# 1wire_temp.net
KiCad netlist of a schematic drawn in EAGLE
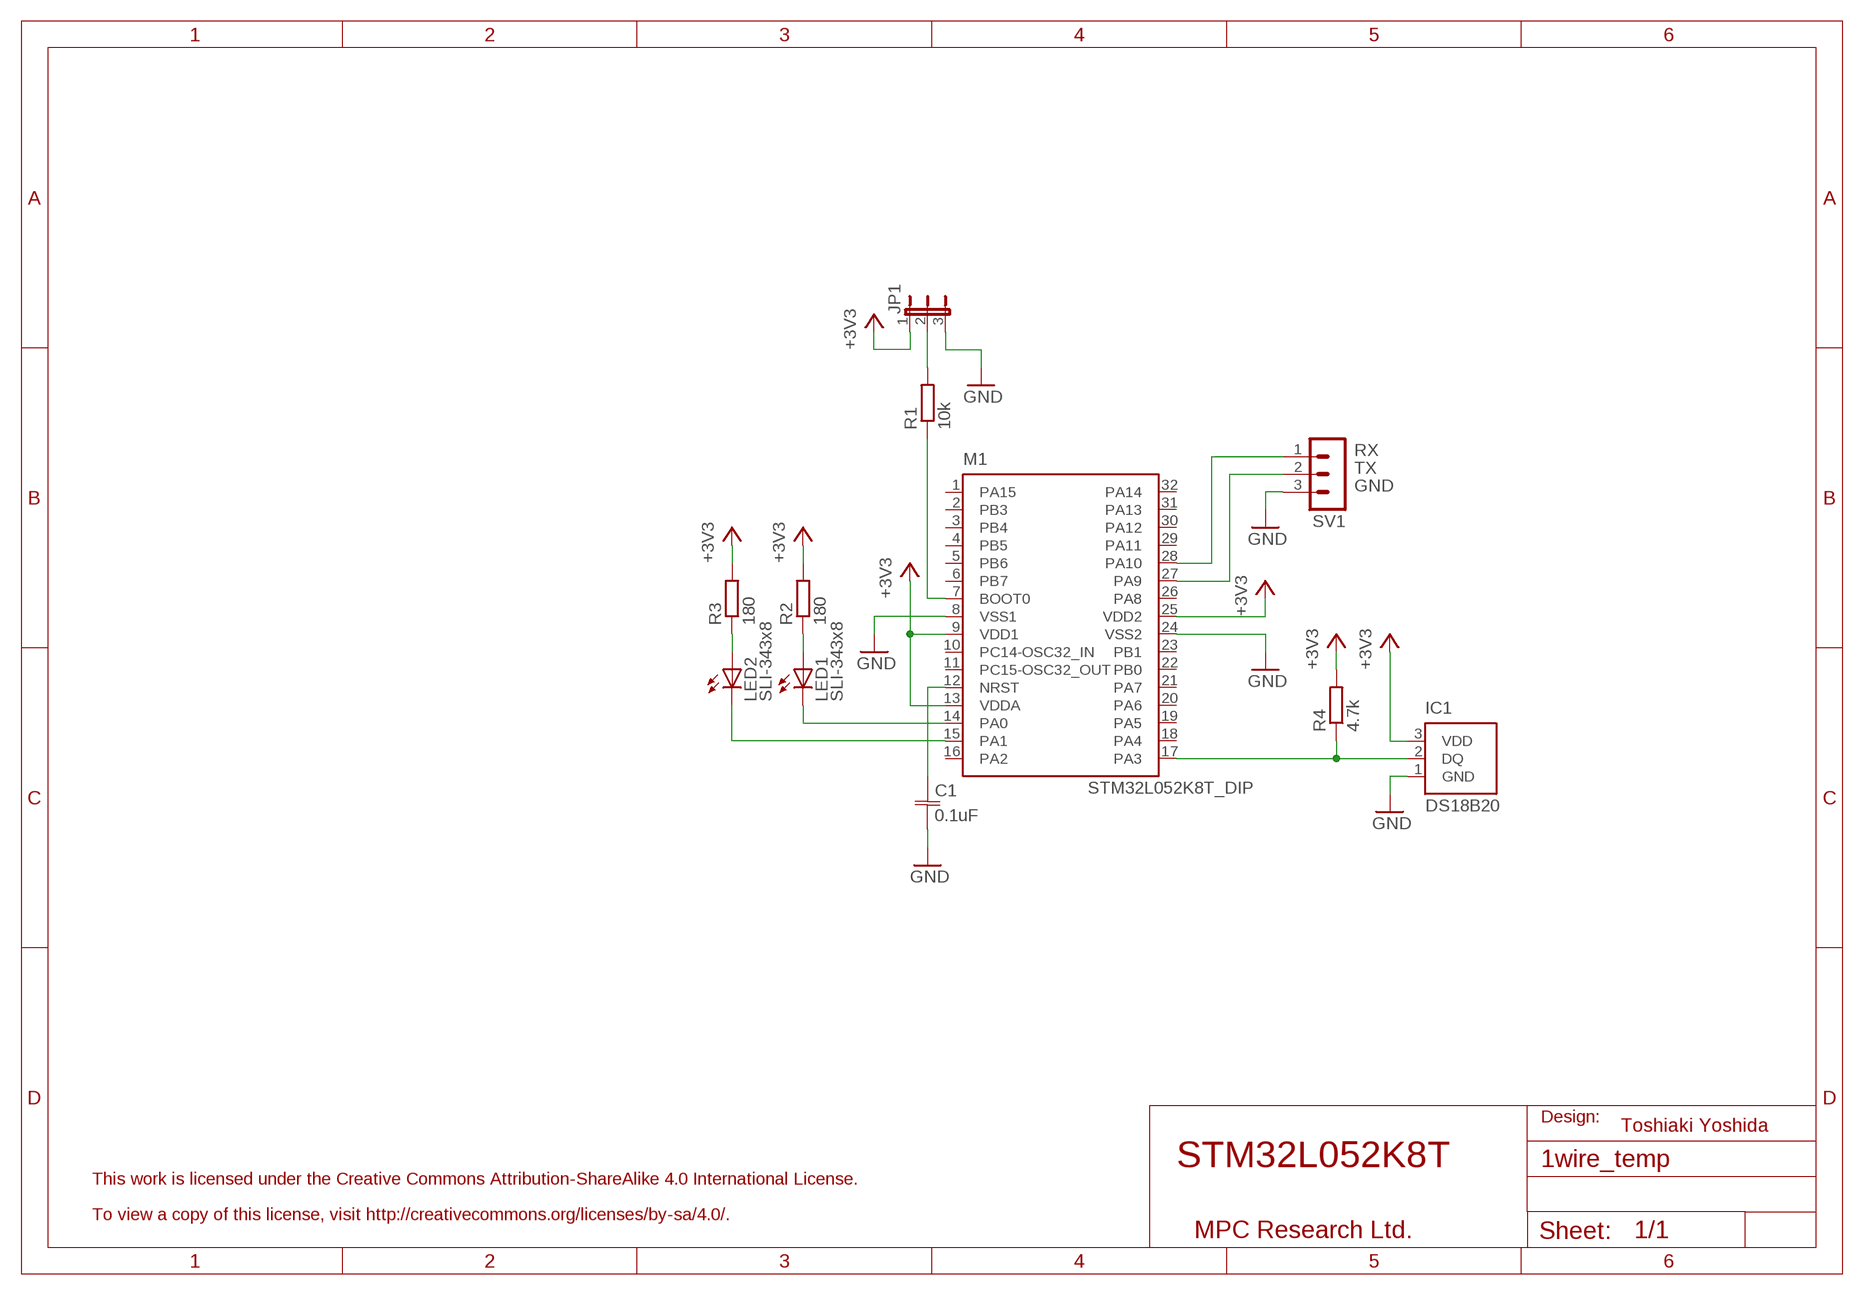
[diagram p0: schematic, sheet 1]

(export (version "E")
  (design (tool "Eeschema 10.0.6"))
  (components
    (comp (ref "C1")
      (value "0.1uF")
      (footprint "eagle-import:C050-024X044")
      (libsource (lib "eagle-import") (part "C-JIS050-024X044"))
    )
    (comp (ref "IC1")
      (value "DS18B20")
      (footprint "eagle-import:TO92-")
      (libsource (lib "eagle-import") (part "DS18B20"))
    )
    (comp (ref "JP1")
      (value "JP2E")
      (footprint "eagle-import:JP2")
      (libsource (lib "eagle-import") (part "JP2E"))
    )
    (comp (ref "LED1")
      (value "SLI-343x8")
      (footprint "eagle-import:LED3MM")
      (libsource (lib "eagle-import") (part "LED3MM"))
    )
    (comp (ref "LED2")
      (value "SLI-343x8")
      (footprint "eagle-import:LED3MM")
      (libsource (lib "eagle-import") (part "LED3MM"))
    )
    (comp (ref "M1")
      (value "STM32L052K8T_DIP")
      (footprint "eagle-import:DIP32")
      (libsource (lib "eagle-import") (part "STM32L052K8T_DIP"))
    )
    (comp (ref "R1")
      (value "10k")
      (footprint "eagle-import:0207_2V")
      (libsource (lib "eagle-import") (part "R-EU_0207/2V"))
    )
    (comp (ref "R2")
      (value "180")
      (footprint "eagle-import:0207_2V")
      (libsource (lib "eagle-import") (part "R-EU_0207/2V"))
    )
    (comp (ref "R3")
      (value "180")
      (footprint "eagle-import:0207_2V")
      (libsource (lib "eagle-import") (part "R-EU_0207/2V"))
    )
    (comp (ref "R4")
      (value "4.7k")
      (footprint "eagle-import:0207_2V")
      (libsource (lib "eagle-import") (part "R-EU_0207/2V"))
    )
    (comp (ref "SV1")
      (value "MA03-1")
      (footprint "eagle-import:MA03-1")
      (libsource (lib "eagle-import") (part "MA03-1"))
    )
  )
  (nets
    (net (code "1") (name "+3V3") (class "Default")
      (node (ref "IC1") (pin "3") (pinfunction "VDD_3") (pintype "power_in"))
      (node (ref "JP1") (pin "1") (pinfunction "1_1") (pintype "passive"))
      (node (ref "M1") (pin "13") (pinfunction "VDDA_13") (pintype "power_in"))
      (node (ref "M1") (pin "25") (pinfunction "VDD2_25") (pintype "bidirectional"))
      (node (ref "M1") (pin "9") (pinfunction "VDD1_9") (pintype "power_in"))
      (node (ref "R2") (pin "2") (pinfunction "2_2") (pintype "passive"))
      (node (ref "R3") (pin "2") (pinfunction "2_2") (pintype "passive"))
      (node (ref "R4") (pin "2") (pinfunction "2_2") (pintype "passive"))
    )
    (net (code "2") (name "GND") (class "Default")
      (node (ref "C1") (pin "2") (pinfunction "2_2") (pintype "passive"))
      (node (ref "IC1") (pin "1") (pinfunction "GND_1") (pintype "power_in"))
      (node (ref "JP1") (pin "3") (pinfunction "3_3") (pintype "passive"))
      (node (ref "M1") (pin "24") (pinfunction "VSS2_24") (pintype "power_in"))
      (node (ref "M1") (pin "8") (pinfunction "VSS1_8") (pintype "power_in"))
      (node (ref "SV1") (pin "3") (pinfunction "3_3") (pintype "passive"))
    )
    (net (code "3") (name "Net-(IC1-DQ)") (class "Default")
      (node (ref "IC1") (pin "2") (pinfunction "DQ_2") (pintype "bidirectional"))
      (node (ref "M1") (pin "17") (pinfunction "PA3_17") (pintype "bidirectional"))
      (node (ref "R4") (pin "1") (pinfunction "1_1") (pintype "passive"))
    )
    (net (code "4") (name "Net-(JP1-Pad2)") (class "Default")
      (node (ref "JP1") (pin "2") (pinfunction "2_2") (pintype "passive"))
      (node (ref "R1") (pin "2") (pinfunction "2_2") (pintype "passive"))
    )
    (net (code "5") (name "Net-(LED1-C)") (class "Default")
      (node (ref "LED1") (pin "K") (pinfunction "C_K") (pintype "passive"))
      (node (ref "M1") (pin "14") (pinfunction "PA0_14") (pintype "bidirectional"))
    )
    (net (code "6") (name "Net-(LED1-PadA)") (class "Default")
      (node (ref "LED1") (pin "A") (pinfunction "A_A") (pintype "passive"))
      (node (ref "R2") (pin "1") (pinfunction "1_1") (pintype "passive"))
    )
    (net (code "7") (name "Net-(LED2-C)") (class "Default")
      (node (ref "LED2") (pin "K") (pinfunction "C_K") (pintype "passive"))
      (node (ref "M1") (pin "15") (pinfunction "PA1_15") (pintype "bidirectional"))
    )
    (net (code "8") (name "Net-(LED2-PadA)") (class "Default")
      (node (ref "LED2") (pin "A") (pinfunction "A_A") (pintype "passive"))
      (node (ref "R3") (pin "1") (pinfunction "1_1") (pintype "passive"))
    )
    (net (code "9") (name "Net-(M1-BOOT0)") (class "Default")
      (node (ref "M1") (pin "7") (pinfunction "BOOT0_7") (pintype "bidirectional"))
      (node (ref "R1") (pin "1") (pinfunction "1_1") (pintype "passive"))
    )
    (net (code "10") (name "Net-(M1-NRST)") (class "Default")
      (node (ref "C1") (pin "1") (pinfunction "1_1") (pintype "passive"))
      (node (ref "M1") (pin "12") (pinfunction "NRST_12") (pintype "bidirectional"))
    )
    (net (code "11") (name "Net-(M1-PA9)") (class "Default")
      (node (ref "M1") (pin "27") (pinfunction "PA9_27") (pintype "bidirectional"))
      (node (ref "SV1") (pin "2") (pinfunction "2_2") (pintype "passive"))
    )
    (net (code "12") (name "Net-(M1-PA10)") (class "Default")
      (node (ref "M1") (pin "28") (pinfunction "PA10_28") (pintype "bidirectional"))
      (node (ref "SV1") (pin "1") (pinfunction "1_1") (pintype "passive"))
    )
    (net (code "13") (name "unconnected-(M1-PA2-Pad16)") (class "Default")
      (node (ref "M1") (pin "16") (pinfunction "PA2_16") (pintype "bidirectional"))
    )
    (net (code "14") (name "unconnected-(M1-PA4-Pad18)") (class "Default")
      (node (ref "M1") (pin "18") (pinfunction "PA4_18") (pintype "bidirectional"))
    )
    (net (code "15") (name "unconnected-(M1-PA5-Pad19)") (class "Default")
      (node (ref "M1") (pin "19") (pinfunction "PA5_19") (pintype "bidirectional"))
    )
    (net (code "16") (name "unconnected-(M1-PA6-Pad20)") (class "Default")
      (node (ref "M1") (pin "20") (pinfunction "PA6_20") (pintype "bidirectional"))
    )
    (net (code "17") (name "unconnected-(M1-PA7-Pad21)") (class "Default")
      (node (ref "M1") (pin "21") (pinfunction "PA7_21") (pintype "bidirectional"))
    )
    (net (code "18") (name "unconnected-(M1-PA8-Pad26)") (class "Default")
      (node (ref "M1") (pin "26") (pinfunction "PA8_26") (pintype "bidirectional"))
    )
    (net (code "19") (name "unconnected-(M1-PA11-Pad29)") (class "Default")
      (node (ref "M1") (pin "29") (pinfunction "PA11_29") (pintype "bidirectional"))
    )
    (net (code "20") (name "unconnected-(M1-PA12-Pad30)") (class "Default")
      (node (ref "M1") (pin "30") (pinfunction "PA12_30") (pintype "bidirectional"))
    )
    (net (code "21") (name "unconnected-(M1-PA13-Pad31)") (class "Default")
      (node (ref "M1") (pin "31") (pinfunction "PA13_31") (pintype "bidirectional"))
    )
    (net (code "22") (name "unconnected-(M1-PA14-Pad32)") (class "Default")
      (node (ref "M1") (pin "32") (pinfunction "PA14_32") (pintype "bidirectional"))
    )
    (net (code "23") (name "unconnected-(M1-PA15-Pad1)") (class "Default")
      (node (ref "M1") (pin "1") (pinfunction "PA15_1") (pintype "bidirectional"))
    )
    (net (code "24") (name "unconnected-(M1-PB0-Pad22)") (class "Default")
      (node (ref "M1") (pin "22") (pinfunction "PB0_22") (pintype "bidirectional"))
    )
    (net (code "25") (name "unconnected-(M1-PB1-Pad23)") (class "Default")
      (node (ref "M1") (pin "23") (pinfunction "PB1_23") (pintype "bidirectional"))
    )
    (net (code "26") (name "unconnected-(M1-PB3-Pad2)") (class "Default")
      (node (ref "M1") (pin "2") (pinfunction "PB3_2") (pintype "bidirectional"))
    )
    (net (code "27") (name "unconnected-(M1-PB4-Pad3)") (class "Default")
      (node (ref "M1") (pin "3") (pinfunction "PB4_3") (pintype "bidirectional"))
    )
    (net (code "28") (name "unconnected-(M1-PB5-Pad4)") (class "Default")
      (node (ref "M1") (pin "4") (pinfunction "PB5_4") (pintype "bidirectional"))
    )
    (net (code "29") (name "unconnected-(M1-PB6-Pad5)") (class "Default")
      (node (ref "M1") (pin "5") (pinfunction "PB6_5") (pintype "bidirectional"))
    )
    (net (code "30") (name "unconnected-(M1-PB7-Pad6)") (class "Default")
      (node (ref "M1") (pin "6") (pinfunction "PB7_6") (pintype "bidirectional"))
    )
    (net (code "31") (name "unconnected-(M1-PC14-OSC32_IN-Pad10)") (class "Default")
      (node (ref "M1") (pin "10") (pinfunction "PC14-OSC32_IN_10") (pintype "bidirectional"))
    )
    (net (code "32") (name "unconnected-(M1-PC15-OSC32_OUT-Pad11)") (class "Default")
      (node (ref "M1") (pin "11") (pinfunction "PC15-OSC32_OUT_11") (pintype "bidirectional"))
    )
  )
)
